# LED_PCB.net
KiCad netlist of a schematic drawn in Altium Designer
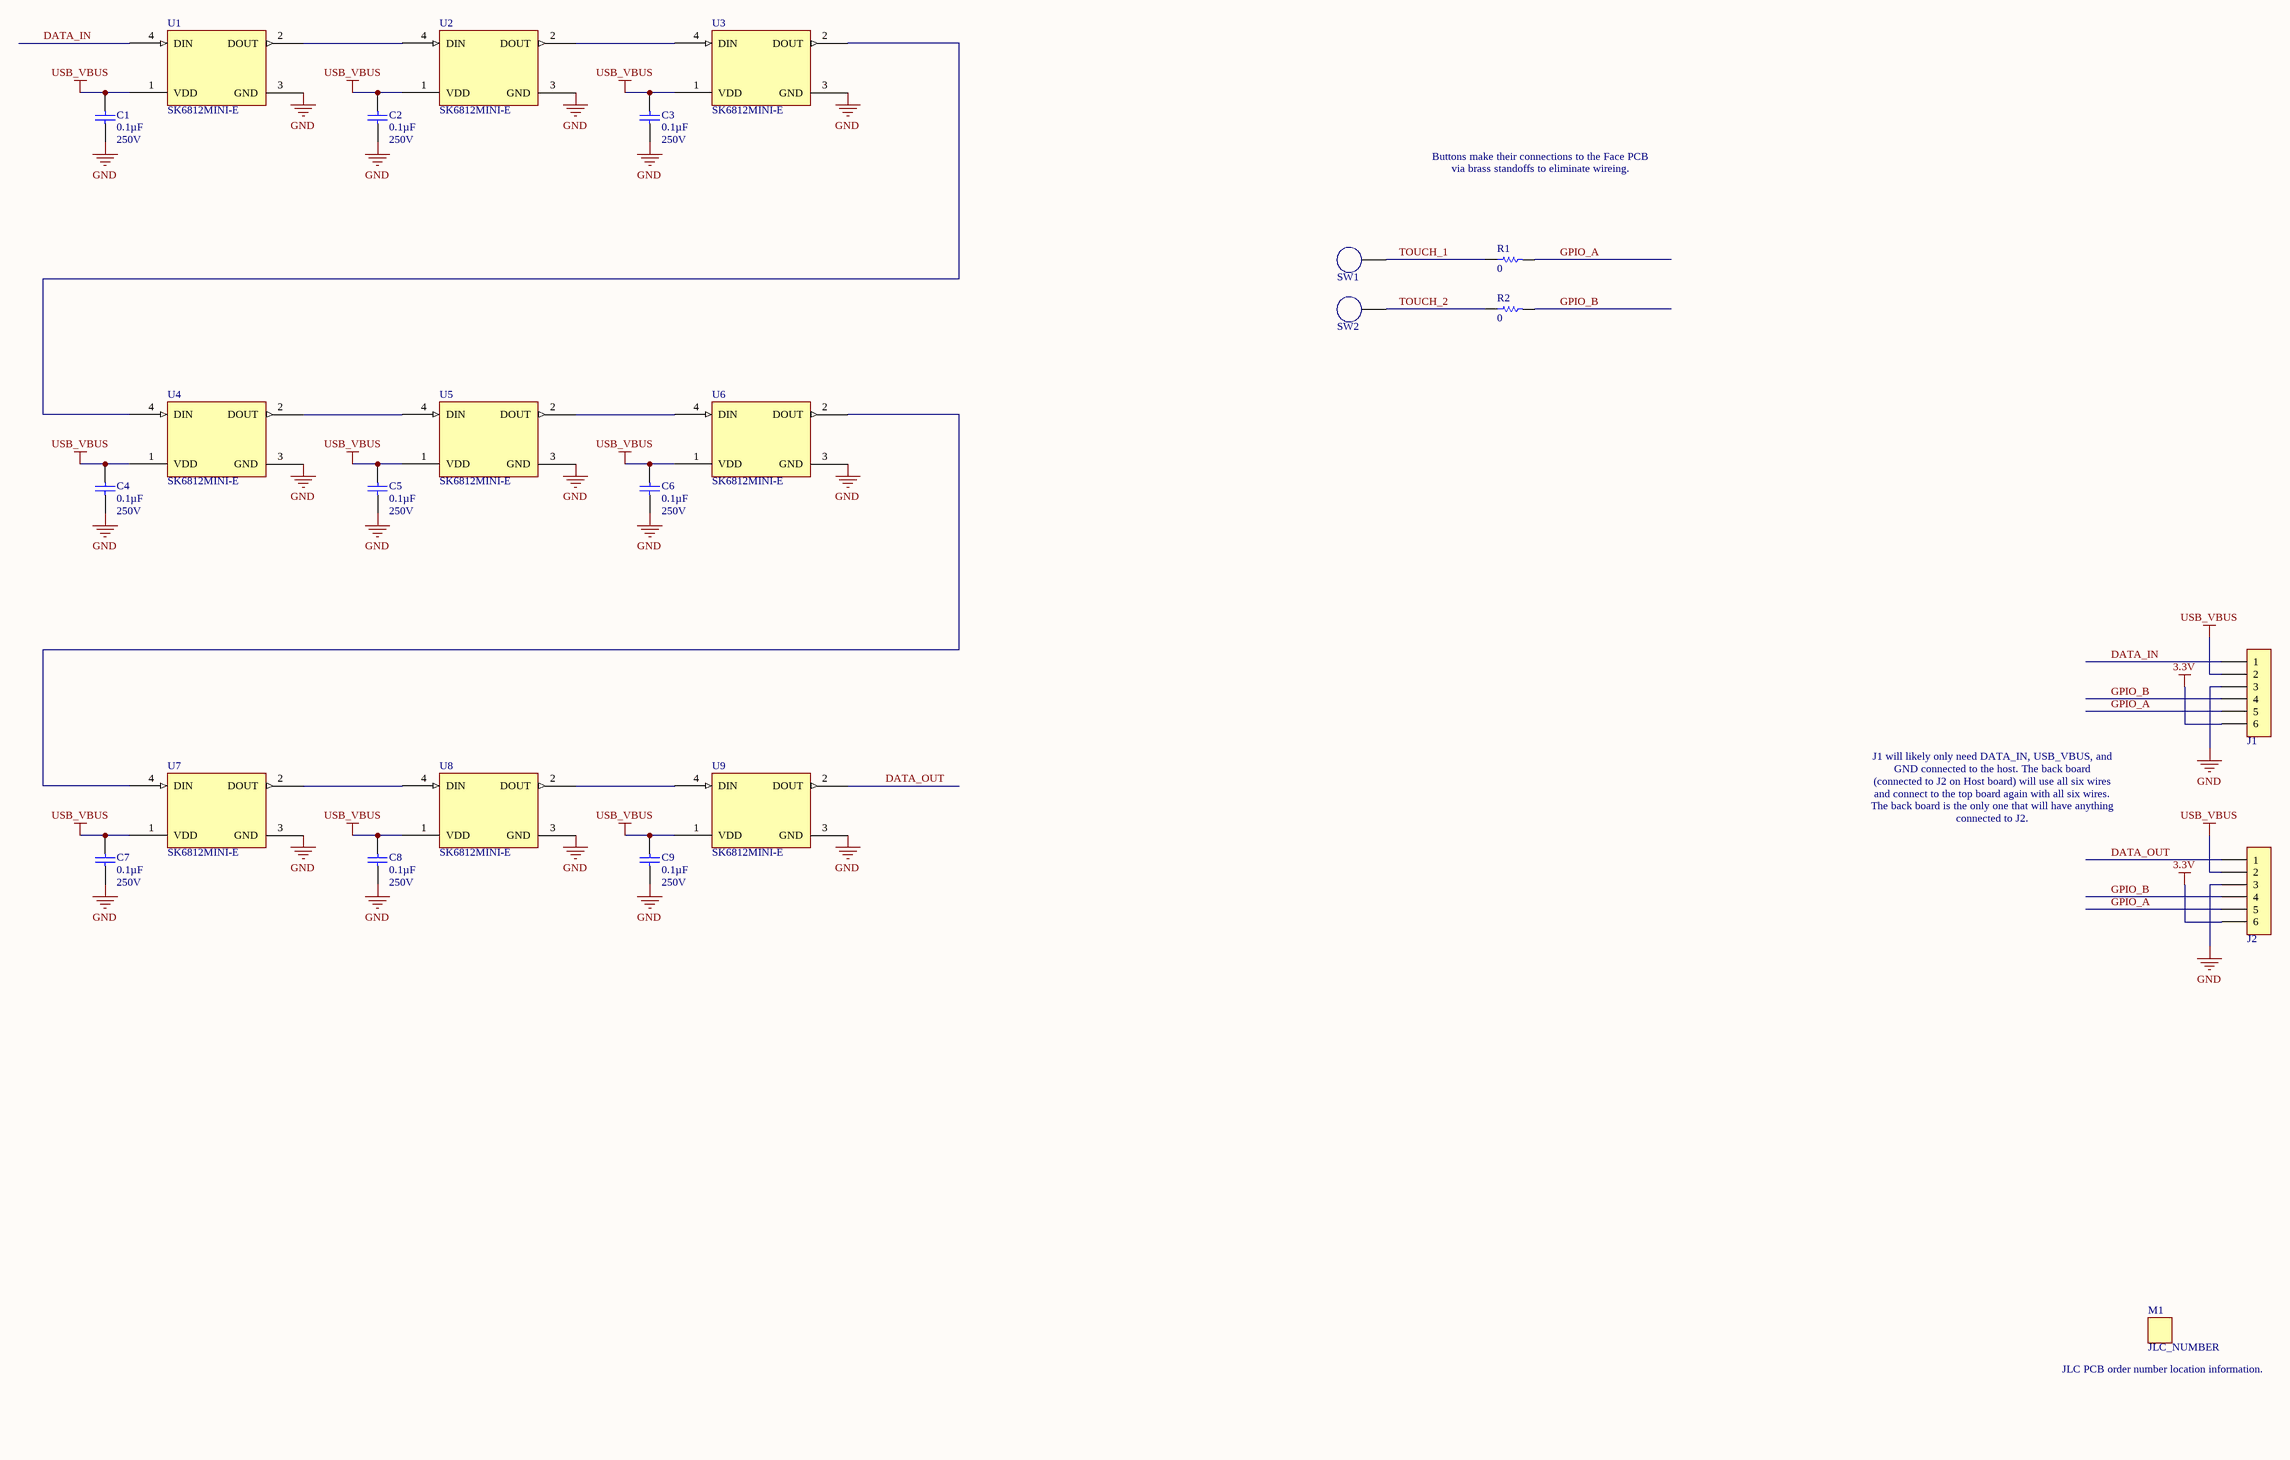
[diagram p0: LED_PCB.SchDoc]

(export (version "E")
  (design (tool "Eeschema 10.0.6"))
  (components
    (comp (ref "C1")
      (value "0.1µF")
      (footprint "Chip0805")
      (description "CAP CER 0.1UF 250V 10% X7T 0805")
      (fields
        (field (name "VOLTAGE") "250V")
        (field (name "PARTNUMBER") "C2012X7T2E104K125AA")
        (field (name "MANUFACTURER") "TDK Corporation")
      )
      (libsource (lib "Passives") (part "CAP"))
    )
    (comp (ref "C2")
      (value "0.1µF")
      (footprint "Chip0805")
      (description "CAP CER 0.1UF 250V 10% X7T 0805")
      (fields
        (field (name "VOLTAGE") "250V")
        (field (name "PARTNUMBER") "C2012X7T2E104K125AA")
        (field (name "MANUFACTURER") "TDK Corporation")
      )
      (libsource (lib "Passives") (part "CAP"))
    )
    (comp (ref "C3")
      (value "0.1µF")
      (footprint "Chip0805")
      (description "CAP CER 0.1UF 250V 10% X7T 0805")
      (fields
        (field (name "VOLTAGE") "250V")
        (field (name "PARTNUMBER") "C2012X7T2E104K125AA")
        (field (name "MANUFACTURER") "TDK Corporation")
      )
      (libsource (lib "Passives") (part "CAP"))
    )
    (comp (ref "C4")
      (value "0.1µF")
      (footprint "Chip0805")
      (description "CAP CER 0.1UF 250V 10% X7T 0805")
      (fields
        (field (name "VOLTAGE") "250V")
        (field (name "PARTNUMBER") "C2012X7T2E104K125AA")
        (field (name "MANUFACTURER") "TDK Corporation")
      )
      (libsource (lib "Passives") (part "CAP"))
    )
    (comp (ref "C5")
      (value "0.1µF")
      (footprint "Chip0805")
      (description "CAP CER 0.1UF 250V 10% X7T 0805")
      (fields
        (field (name "VOLTAGE") "250V")
        (field (name "PARTNUMBER") "C2012X7T2E104K125AA")
        (field (name "MANUFACTURER") "TDK Corporation")
      )
      (libsource (lib "Passives") (part "CAP"))
    )
    (comp (ref "C6")
      (value "0.1µF")
      (footprint "Chip0805")
      (description "CAP CER 0.1UF 250V 10% X7T 0805")
      (fields
        (field (name "VOLTAGE") "250V")
        (field (name "PARTNUMBER") "C2012X7T2E104K125AA")
        (field (name "MANUFACTURER") "TDK Corporation")
      )
      (libsource (lib "Passives") (part "CAP"))
    )
    (comp (ref "C7")
      (value "0.1µF")
      (footprint "Chip0805")
      (description "CAP CER 0.1UF 250V 10% X7T 0805")
      (fields
        (field (name "VOLTAGE") "250V")
        (field (name "PARTNUMBER") "C2012X7T2E104K125AA")
        (field (name "MANUFACTURER") "TDK Corporation")
      )
      (libsource (lib "Passives") (part "CAP"))
    )
    (comp (ref "C8")
      (value "0.1µF")
      (footprint "Chip0805")
      (description "CAP CER 0.1UF 250V 10% X7T 0805")
      (fields
        (field (name "VOLTAGE") "250V")
        (field (name "PARTNUMBER") "C2012X7T2E104K125AA")
        (field (name "MANUFACTURER") "TDK Corporation")
      )
      (libsource (lib "Passives") (part "CAP"))
    )
    (comp (ref "C9")
      (value "0.1µF")
      (footprint "Chip0805")
      (description "CAP CER 0.1UF 250V 10% X7T 0805")
      (fields
        (field (name "VOLTAGE") "250V")
        (field (name "PARTNUMBER") "C2012X7T2E104K125AA")
        (field (name "MANUFACTURER") "TDK Corporation")
      )
      (libsource (lib "Passives") (part "CAP"))
    )
    (comp (ref "J1")
      (value "HEADER_1x6_NO_BOM")
      (footprint "HEADER_1x6_100mil_NP")
      (libsource (lib "Mechanical") (part "HEADER_1x6_NO_BOM"))
    )
    (comp (ref "J2")
      (value "HEADER_1x6_NO_BOM")
      (footprint "HEADER_1x6_100mil_NP")
      (libsource (lib "Mechanical") (part "HEADER_1x6_NO_BOM"))
    )
    (comp (ref "M1")
      (value "JLC_NUMBER")
      (footprint "JLC_NUMBER")
      (description "JLC Order Number Location")
      (libsource (lib "Mechanical") (part "MECH_NO_BOM"))
    )
    (comp (ref "R1")
      (value "0")
      (footprint "Chip0805")
      (description "RES 0.0 OHM 1/8W JUMP 0805 SMD")
      (fields (field (name "PARTNUMBER") "CRCW08050000Z0EA") (field (name "MANUFACTURER") "Vishay Dale"))
      (libsource (lib "Passives") (part "RES"))
    )
    (comp (ref "R2")
      (value "0")
      (footprint "Chip0805")
      (description "RES 0.0 OHM 1/8W JUMP 0805 SMD")
      (fields (field (name "PARTNUMBER") "CRCW08050000Z0EA") (field (name "MANUFACTURER") "Vishay Dale"))
      (libsource (lib "Passives") (part "RES"))
    )
    (comp (ref "SW1")
      (value "TOUCH_PAD_NO_BOM")
      (footprint "TENTED_PAD_5mil")
      (libsource (lib "Mechanical") (part "TOUCH_PAD_NO_BOM"))
    )
    (comp (ref "SW2")
      (value "TOUCH_PAD_NO_BOM")
      (footprint "TENTED_PAD_5mil")
      (libsource (lib "Mechanical") (part "TOUCH_PAD_NO_BOM"))
    )
    (comp (ref "U1")
      (value "SK6812MINI-E")
      (footprint "SK6812MINI-E")
      (description "Addressable RGB LED")
      (fields (field (name "MANUFACTURER") "Adafruit Industries LLC"))
      (libsource (lib "Optoelectronics") (part "SK6812MINI-E"))
    )
    (comp (ref "U2")
      (value "SK6812MINI-E")
      (footprint "SK6812MINI-E")
      (description "Addressable RGB LED")
      (fields (field (name "MANUFACTURER") "Adafruit Industries LLC"))
      (libsource (lib "Optoelectronics") (part "SK6812MINI-E"))
    )
    (comp (ref "U3")
      (value "SK6812MINI-E")
      (footprint "SK6812MINI-E")
      (description "Addressable RGB LED")
      (fields (field (name "MANUFACTURER") "Adafruit Industries LLC"))
      (libsource (lib "Optoelectronics") (part "SK6812MINI-E"))
    )
    (comp (ref "U4")
      (value "SK6812MINI-E")
      (footprint "SK6812MINI-E")
      (description "Addressable RGB LED")
      (fields (field (name "MANUFACTURER") "Adafruit Industries LLC"))
      (libsource (lib "Optoelectronics") (part "SK6812MINI-E"))
    )
    (comp (ref "U5")
      (value "SK6812MINI-E")
      (footprint "SK6812MINI-E")
      (description "Addressable RGB LED")
      (fields (field (name "MANUFACTURER") "Adafruit Industries LLC"))
      (libsource (lib "Optoelectronics") (part "SK6812MINI-E"))
    )
    (comp (ref "U6")
      (value "SK6812MINI-E")
      (footprint "SK6812MINI-E")
      (description "Addressable RGB LED")
      (fields (field (name "MANUFACTURER") "Adafruit Industries LLC"))
      (libsource (lib "Optoelectronics") (part "SK6812MINI-E"))
    )
    (comp (ref "U7")
      (value "SK6812MINI-E")
      (footprint "SK6812MINI-E")
      (description "Addressable RGB LED")
      (fields (field (name "MANUFACTURER") "Adafruit Industries LLC"))
      (libsource (lib "Optoelectronics") (part "SK6812MINI-E"))
    )
    (comp (ref "U8")
      (value "SK6812MINI-E")
      (footprint "SK6812MINI-E")
      (description "Addressable RGB LED")
      (fields (field (name "MANUFACTURER") "Adafruit Industries LLC"))
      (libsource (lib "Optoelectronics") (part "SK6812MINI-E"))
    )
    (comp (ref "U9")
      (value "SK6812MINI-E")
      (footprint "SK6812MINI-E")
      (description "Addressable RGB LED")
      (fields (field (name "MANUFACTURER") "Adafruit Industries LLC"))
      (libsource (lib "Optoelectronics") (part "SK6812MINI-E"))
    )
  )
  (nets
    (net (code "1") (name "/DATA_IN") (class "Default")
      (node (ref "J1") (pin "1") (pinfunction "1_1") (pintype "passive"))
      (node (ref "U1") (pin "4") (pinfunction "DIN_4") (pintype "input"))
    )
    (net (code "2") (name "/DATA_OUT") (class "Default")
      (node (ref "J2") (pin "1") (pinfunction "1_1") (pintype "passive"))
      (node (ref "U9") (pin "2") (pinfunction "DOUT_2") (pintype "output"))
    )
    (net (code "3") (name "/GPIO_A") (class "Default")
      (node (ref "J1") (pin "5") (pinfunction "5_5") (pintype "passive"))
      (node (ref "J2") (pin "5") (pinfunction "5_5") (pintype "passive"))
      (node (ref "R1") (pin "2") (pinfunction "2_2") (pintype "passive"))
    )
    (net (code "4") (name "/GPIO_B") (class "Default")
      (node (ref "J1") (pin "4") (pinfunction "4_4") (pintype "passive"))
      (node (ref "J2") (pin "4") (pinfunction "4_4") (pintype "passive"))
      (node (ref "R2") (pin "2") (pinfunction "2_2") (pintype "passive"))
    )
    (net (code "5") (name "/TOUCH_1") (class "Default")
      (node (ref "R1") (pin "1") (pinfunction "1_1") (pintype "passive"))
      (node (ref "SW1") (pin "1") (pinfunction "1_1") (pintype "passive"))
    )
    (net (code "6") (name "/TOUCH_2") (class "Default")
      (node (ref "R2") (pin "1") (pinfunction "1_1") (pintype "passive"))
      (node (ref "SW2") (pin "1") (pinfunction "1_1") (pintype "passive"))
    )
    (net (code "7") (name "3.3V") (class "Default")
      (node (ref "J1") (pin "6") (pinfunction "6_6") (pintype "passive"))
      (node (ref "J2") (pin "6") (pinfunction "6_6") (pintype "passive"))
    )
    (net (code "8") (name "GND") (class "Default")
      (node (ref "C1") (pin "1") (pinfunction "1_1") (pintype "passive"))
      (node (ref "C2") (pin "1") (pinfunction "1_1") (pintype "passive"))
      (node (ref "C3") (pin "1") (pinfunction "1_1") (pintype "passive"))
      (node (ref "C4") (pin "1") (pinfunction "1_1") (pintype "passive"))
      (node (ref "C5") (pin "1") (pinfunction "1_1") (pintype "passive"))
      (node (ref "C6") (pin "1") (pinfunction "1_1") (pintype "passive"))
      (node (ref "C7") (pin "1") (pinfunction "1_1") (pintype "passive"))
      (node (ref "C8") (pin "1") (pinfunction "1_1") (pintype "passive"))
      (node (ref "C9") (pin "1") (pinfunction "1_1") (pintype "passive"))
      (node (ref "J1") (pin "3") (pinfunction "3_3") (pintype "passive"))
      (node (ref "J2") (pin "3") (pinfunction "3_3") (pintype "passive"))
      (node (ref "U1") (pin "3") (pinfunction "GND_3") (pintype "passive"))
      (node (ref "U2") (pin "3") (pinfunction "GND_3") (pintype "passive"))
      (node (ref "U3") (pin "3") (pinfunction "GND_3") (pintype "passive"))
      (node (ref "U4") (pin "3") (pinfunction "GND_3") (pintype "passive"))
      (node (ref "U5") (pin "3") (pinfunction "GND_3") (pintype "passive"))
      (node (ref "U6") (pin "3") (pinfunction "GND_3") (pintype "passive"))
      (node (ref "U7") (pin "3") (pinfunction "GND_3") (pintype "passive"))
      (node (ref "U8") (pin "3") (pinfunction "GND_3") (pintype "passive"))
      (node (ref "U9") (pin "3") (pinfunction "GND_3") (pintype "passive"))
    )
    (net (code "9") (name "Net-(U1-DOUT)") (class "Default")
      (node (ref "U1") (pin "2") (pinfunction "DOUT_2") (pintype "output"))
      (node (ref "U2") (pin "4") (pinfunction "DIN_4") (pintype "input"))
    )
    (net (code "10") (name "Net-(U2-DOUT)") (class "Default")
      (node (ref "U2") (pin "2") (pinfunction "DOUT_2") (pintype "output"))
      (node (ref "U3") (pin "4") (pinfunction "DIN_4") (pintype "input"))
    )
    (net (code "11") (name "Net-(U3-DOUT)") (class "Default")
      (node (ref "U3") (pin "2") (pinfunction "DOUT_2") (pintype "output"))
      (node (ref "U4") (pin "4") (pinfunction "DIN_4") (pintype "input"))
    )
    (net (code "12") (name "Net-(U4-DOUT)") (class "Default")
      (node (ref "U4") (pin "2") (pinfunction "DOUT_2") (pintype "output"))
      (node (ref "U5") (pin "4") (pinfunction "DIN_4") (pintype "input"))
    )
    (net (code "13") (name "Net-(U5-DOUT)") (class "Default")
      (node (ref "U5") (pin "2") (pinfunction "DOUT_2") (pintype "output"))
      (node (ref "U6") (pin "4") (pinfunction "DIN_4") (pintype "input"))
    )
    (net (code "14") (name "Net-(U6-DOUT)") (class "Default")
      (node (ref "U6") (pin "2") (pinfunction "DOUT_2") (pintype "output"))
      (node (ref "U7") (pin "4") (pinfunction "DIN_4") (pintype "input"))
    )
    (net (code "15") (name "Net-(U7-DOUT)") (class "Default")
      (node (ref "U7") (pin "2") (pinfunction "DOUT_2") (pintype "output"))
      (node (ref "U8") (pin "4") (pinfunction "DIN_4") (pintype "input"))
    )
    (net (code "16") (name "Net-(U8-DOUT)") (class "Default")
      (node (ref "U8") (pin "2") (pinfunction "DOUT_2") (pintype "output"))
      (node (ref "U9") (pin "4") (pinfunction "DIN_4") (pintype "input"))
    )
    (net (code "17") (name "USB_VBUS") (class "Default")
      (node (ref "C1") (pin "2") (pinfunction "2_2") (pintype "passive"))
      (node (ref "C2") (pin "2") (pinfunction "2_2") (pintype "passive"))
      (node (ref "C3") (pin "2") (pinfunction "2_2") (pintype "passive"))
      (node (ref "C4") (pin "2") (pinfunction "2_2") (pintype "passive"))
      (node (ref "C5") (pin "2") (pinfunction "2_2") (pintype "passive"))
      (node (ref "C6") (pin "2") (pinfunction "2_2") (pintype "passive"))
      (node (ref "C7") (pin "2") (pinfunction "2_2") (pintype "passive"))
      (node (ref "C8") (pin "2") (pinfunction "2_2") (pintype "passive"))
      (node (ref "C9") (pin "2") (pinfunction "2_2") (pintype "passive"))
      (node (ref "J1") (pin "2") (pinfunction "2_2") (pintype "passive"))
      (node (ref "J2") (pin "2") (pinfunction "2_2") (pintype "passive"))
      (node (ref "U1") (pin "1") (pinfunction "VDD_1") (pintype "passive"))
      (node (ref "U2") (pin "1") (pinfunction "VDD_1") (pintype "passive"))
      (node (ref "U3") (pin "1") (pinfunction "VDD_1") (pintype "passive"))
      (node (ref "U4") (pin "1") (pinfunction "VDD_1") (pintype "passive"))
      (node (ref "U5") (pin "1") (pinfunction "VDD_1") (pintype "passive"))
      (node (ref "U6") (pin "1") (pinfunction "VDD_1") (pintype "passive"))
      (node (ref "U7") (pin "1") (pinfunction "VDD_1") (pintype "passive"))
      (node (ref "U8") (pin "1") (pinfunction "VDD_1") (pintype "passive"))
      (node (ref "U9") (pin "1") (pinfunction "VDD_1") (pintype "passive"))
    )
  )
)
